# can.net
KiCad netlist of a schematic drawn in Altium Designer
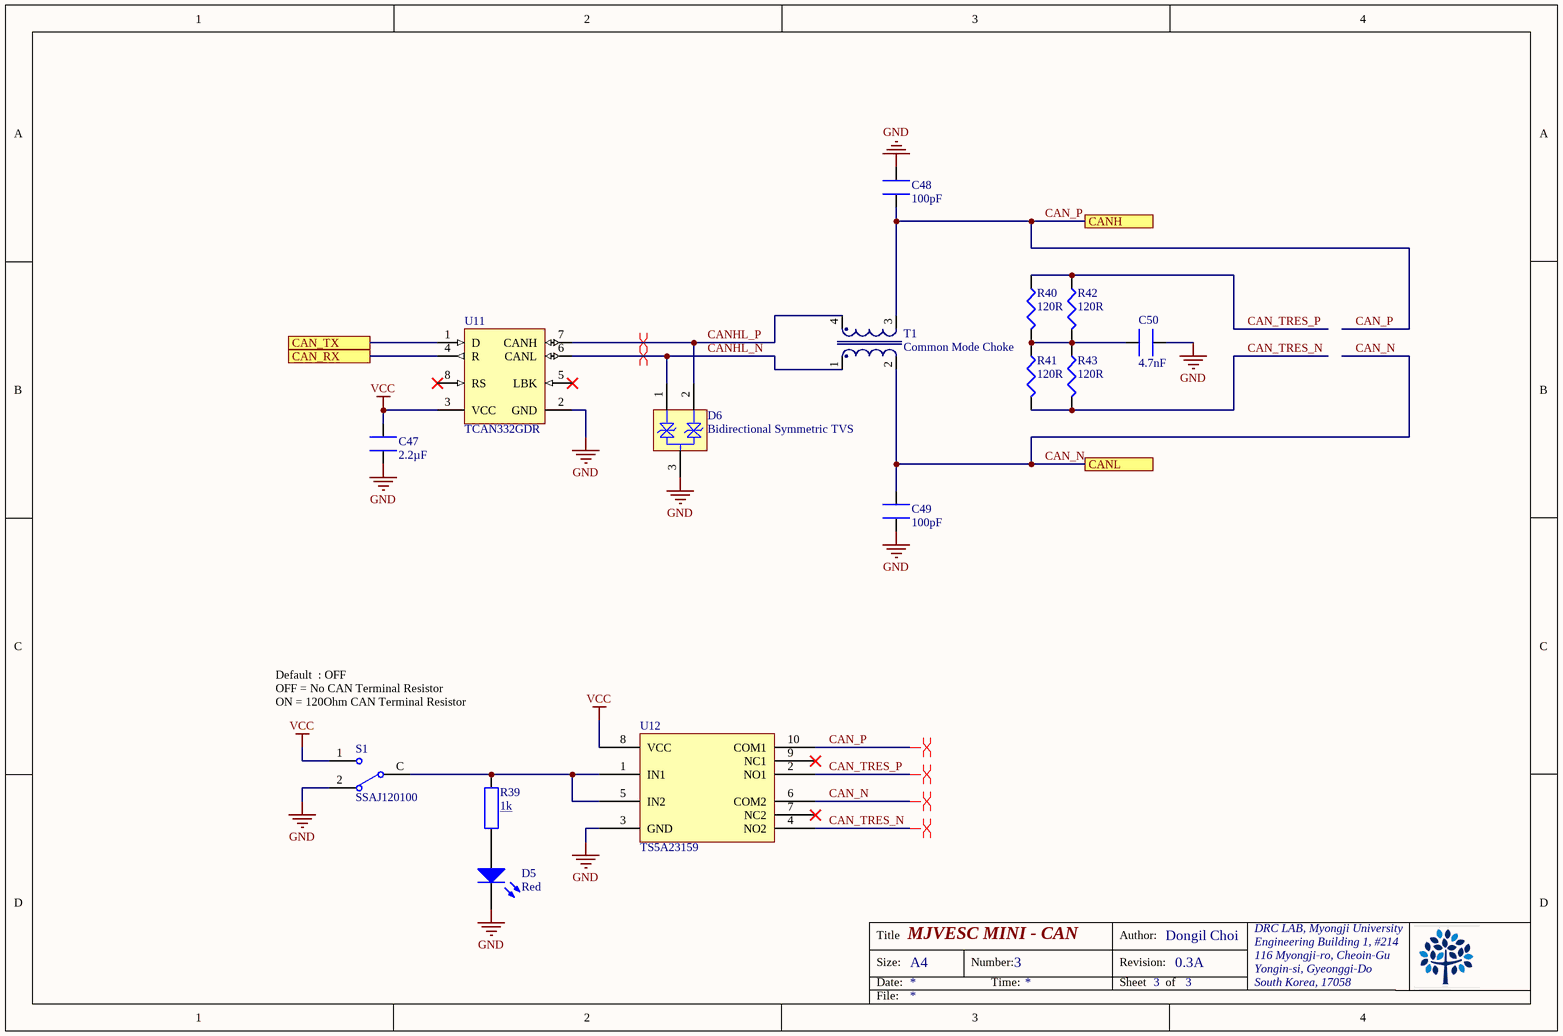
[diagram p0: can.SchDoc]

(export (version "E")
  (design (tool "Eeschema 10.0.6"))
  (components
    (comp (ref "C47")
      (value "2.2µF")
      (footprint "CAP 0603/1608")
      (description "CAP CER 2.2UF 16V X5R 0603")
      (fields
        (field (name "MANUFACTURER") "Murata Electronics North America")
        (field (name "MANUFACTURER PART NUMBER") "GRM188R61C225KE15D")
      )
      (libsource (lib "CustomComponents") (part "GRM188R61C225KE15D"))
    )
    (comp (ref "C48")
      (value "100pF")
      (footprint "CAP 0402/1005")
      (description "CAP CER 100pF 50V NP0 0402")
      (fields (field (name "PARTNUMBER") "GRM1555C1H101GA01D"))
      (libsource (lib "CustomComponents") (part "GRM1885C1H222JA01D"))
    )
    (comp (ref "C49")
      (value "100pF")
      (footprint "CAP 0402/1005")
      (description "CAP CER 100pF 50V NP0 0402")
      (fields (field (name "PARTNUMBER") "GRM1555C1H101GA01D"))
      (libsource (lib "CustomComponents") (part "GRM1885C1H222JA01D"))
    )
    (comp (ref "C50")
      (value "4.7nF")
      (footprint "CAP 0603/1608")
      (description "CAP CER 4.7nF 50V NP0 0603")
      (fields (field (name "PARTNUMBER") "GRM1887U1H472JA01D"))
      (libsource (lib "CustomComponents") (part "GRM1885C1H222JA01D"))
    )
    (comp (ref "D5")
      (value "Red")
      (footprint "LED 0603/1608 RED")
      (description "Typical INFRARED GaAs LED")
      (fields (field (name "PARTNUMBER") "LTST-C191KRKT") (field (name "PUBLISHER") "Altium Limited"))
      (libsource (lib "Miscellaneous Devices") (part "LED0"))
    )
    (comp (ref "D6")
      (value "Bidirectional Symmetric TVS")
      (footprint "SOT23-3L")
      (description "Bi-directional Low Capacitance TVS Diode, -55 to 125 degC, TSLP-3-1, Reel, Green")
      (fields (field (name "PARTNUMBER") "VCAN26A2-03S-E3-08"))
      (libsource (lib "Infineon_ESD_&_EMI") (part "ESD8V0L2B-03L"))
    )
    (comp (ref "R39")
      (value "1k")
      (footprint "RES 0603/1608")
      (description "RES SMD 1K OHM 1% 1/10W 0603")
      (fields (field (name "MANUFACTURER") "Yageo") (field (name "TOLERANCE") "±1%"))
      (libsource (lib "CustomComponents") (part "RC0603FR-071KL"))
    )
    (comp (ref "R40")
      (value "120R")
      (footprint "RES 0603/1608")
      (description "RES SMD 120R OHM 1% 1/10W 0603")
      (fields (field (name "PARTNUMBER") "RC0603FR-07120RL") (field (name "PUBLISHER") "Altium Limited"))
      (libsource (lib "Miscellaneous Devices") (part "Res3"))
    )
    (comp (ref "R41")
      (value "120R")
      (footprint "RES 0603/1608")
      (description "RES SMD 120R OHM 1% 1/10W 0603")
      (fields (field (name "PARTNUMBER") "RC0603FR-07120RL") (field (name "PUBLISHER") "Altium Limited"))
      (libsource (lib "Miscellaneous Devices") (part "Res3"))
    )
    (comp (ref "R42")
      (value "120R")
      (footprint "RES 0603/1608")
      (description "RES SMD 120R OHM 1% 1/10W 0603")
      (fields (field (name "PARTNUMBER") "RC0603FR-07120RL") (field (name "PUBLISHER") "Altium Limited"))
      (libsource (lib "Miscellaneous Devices") (part "Res3"))
    )
    (comp (ref "R43")
      (value "120R")
      (footprint "RES 0603/1608")
      (description "RES SMD 120R OHM 1% 1/10W 0603")
      (fields (field (name "PARTNUMBER") "RC0603FR-07120RL") (field (name "PUBLISHER") "Altium Limited"))
      (libsource (lib "Miscellaneous Devices") (part "Res3"))
    )
    (comp (ref "S1")
      (value "SSAJ120100")
      (footprint "SSAJ120100")
      (description "SPDT Subminiature Toggle Switch, Right Angle Mounting, Vertical Actuation")
      (fields (field (name "PUBLISHER") "Altium Limited"))
      (libsource (lib "Miscellaneous Devices") (part "SW-SPDT"))
    )
    (comp (ref "T1")
      (value "Common Mode Choke")
      (footprint "SRF4532-101Y")
      (description "Dual Coil - Common Mode Choke, 4-Terminal, THT, MID-D11, Bobbin-070-5627")
      (fields (field (name "PARTNUMBER") "SRF4532-101Y"))
      (libsource (lib "Wurth_Electronics_Midcom_Altium_Packages_ALTIUM-MID-DC16US") (part "MID-D11, 070-5627"))
    )
    (comp (ref "U11")
      (value "TCAN332GDR")
      (footprint "D0008A_N")
      (description "3.3V CAN Transceiver, 5Mbps")
      (fields (field (name "MANUFACTURER") "Texas Instruments"))
      (libsource (lib "TCAN332GDR") (part "TCAN332GDR"))
    )
    (comp (ref "U12")
      (value "TS5A23159")
      (footprint "RSE10")
      (description "1-Ω 2-Channel SPDT Analog Switch")
      (fields (field (name "PARTNUMBER") "TS5A23159RSER"))
      (libsource (lib "Multiplexer") (part "TI TS5A23159"))
    )
  )
  (nets
    (net (code "1") (name "/CANHL_N") (class "Default")
      (node (ref "D6") (pin "1") (pinfunction "C_1") (pintype "passive"))
      (node (ref "T1") (pin "1") (pinfunction "1_1") (pintype "passive"))
      (node (ref "U11") (pin "6") (pinfunction "CANL_6") (pintype "bidirectional"))
    )
    (net (code "2") (name "/CANHL_P") (class "Default")
      (node (ref "D6") (pin "2") (pinfunction "C_2") (pintype "passive"))
      (node (ref "T1") (pin "4") (pinfunction "4_4") (pintype "passive"))
      (node (ref "U11") (pin "7") (pinfunction "CANH_7") (pintype "bidirectional"))
    )
    (net (code "3") (name "/CAN_N") (class "Default")
      (node (ref "C49") (pin "1") (pinfunction "1_1") (pintype "passive"))
      (node (ref "T1") (pin "2") (pinfunction "2_2") (pintype "passive"))
      (node (ref "U12") (pin "6") (pinfunction "COM2_6") (pintype "passive"))
    )
    (net (code "4") (name "/CAN_P") (class "Default")
      (node (ref "C48") (pin "2") (pinfunction "2_2") (pintype "passive"))
      (node (ref "T1") (pin "3") (pinfunction "3_3") (pintype "passive"))
      (node (ref "U12") (pin "10") (pinfunction "COM1_10") (pintype "passive"))
    )
    (net (code "5") (name "/CAN_RX") (class "Default")
      (node (ref "U11") (pin "4") (pinfunction "R_4") (pintype "output"))
    )
    (net (code "6") (name "/CAN_TRES_N") (class "Default")
      (node (ref "R41") (pin "2") (pinfunction "2_2") (pintype "passive"))
      (node (ref "R43") (pin "2") (pinfunction "2_2") (pintype "passive"))
      (node (ref "U12") (pin "4") (pinfunction "NO2_4") (pintype "passive"))
    )
    (net (code "7") (name "/CAN_TRES_P") (class "Default")
      (node (ref "R40") (pin "1") (pinfunction "1_1") (pintype "passive"))
      (node (ref "R42") (pin "1") (pinfunction "1_1") (pintype "passive"))
      (node (ref "U12") (pin "2") (pinfunction "NO1_2") (pintype "passive"))
    )
    (net (code "8") (name "/CAN_TX") (class "Default")
      (node (ref "U11") (pin "1") (pinfunction "D_1") (pintype "input"))
    )
    (net (code "9") (name "GND") (class "Default")
      (node (ref "C47") (pin "1") (pinfunction "1_1") (pintype "passive"))
      (node (ref "C48") (pin "1") (pinfunction "1_1") (pintype "passive"))
      (node (ref "C49") (pin "2") (pinfunction "2_2") (pintype "passive"))
      (node (ref "C50") (pin "2") (pinfunction "2_2") (pintype "passive"))
      (node (ref "D5") (pin "2") (pinfunction "K_2") (pintype "passive"))
      (node (ref "D6") (pin "3") (pinfunction "C_3") (pintype "passive"))
      (node (ref "S1") (pin "2") (pinfunction "2_2") (pintype "passive"))
      (node (ref "U11") (pin "2") (pinfunction "GND_2") (pintype "power_in"))
      (node (ref "U12") (pin "3") (pinfunction "GND_3") (pintype "passive"))
    )
    (net (code "10") (name "Net-(C50-Pad1)") (class "Default")
      (node (ref "C50") (pin "1") (pinfunction "1_1") (pintype "passive"))
      (node (ref "R40") (pin "2") (pinfunction "2_2") (pintype "passive"))
      (node (ref "R41") (pin "1") (pinfunction "1_1") (pintype "passive"))
      (node (ref "R42") (pin "2") (pinfunction "2_2") (pintype "passive"))
      (node (ref "R43") (pin "1") (pinfunction "1_1") (pintype "passive"))
    )
    (net (code "11") (name "Net-(D5-A)") (class "Default")
      (node (ref "D5") (pin "1") (pinfunction "A_1") (pintype "passive"))
      (node (ref "R39") (pin "2") (pinfunction "0_2") (pintype "passive"))
    )
    (net (code "12") (name "Net-(U12-IN1)") (class "Default")
      (node (ref "R39") (pin "1") (pinfunction "0_1") (pintype "passive"))
      (node (ref "S1") (pin "C") (pinfunction "C_C") (pintype "passive"))
      (node (ref "U12") (pin "1") (pinfunction "IN1_1") (pintype "passive"))
      (node (ref "U12") (pin "5") (pinfunction "IN2_5") (pintype "passive"))
    )
    (net (code "13") (name "VCC") (class "Default")
      (node (ref "C47") (pin "2") (pinfunction "2_2") (pintype "passive"))
      (node (ref "S1") (pin "1") (pinfunction "1_1") (pintype "passive"))
      (node (ref "U11") (pin "3") (pinfunction "VCC_3") (pintype "power_in"))
      (node (ref "U12") (pin "8") (pinfunction "VCC_8") (pintype "passive"))
    )
    (net (code "14") (name "unconnected-(U11-LBK-Pad5)") (class "Default")
      (node (ref "U11") (pin "5") (pinfunction "LBK_5") (pintype "input+no_connect"))
    )
    (net (code "15") (name "unconnected-(U11-RS-Pad8)") (class "Default")
      (node (ref "U11") (pin "8") (pinfunction "RS_8") (pintype "input+no_connect"))
    )
    (net (code "16") (name "unconnected-(U12-NC1-Pad9)") (class "Default")
      (node (ref "U12") (pin "9") (pinfunction "NC1_9") (pintype "passive+no_connect"))
    )
    (net (code "17") (name "unconnected-(U12-NC2-Pad7)") (class "Default")
      (node (ref "U12") (pin "7") (pinfunction "NC2_7") (pintype "passive+no_connect"))
    )
  )
)
